# logicShifter2.net
KiCad netlist of a schematic drawn in EAGLE
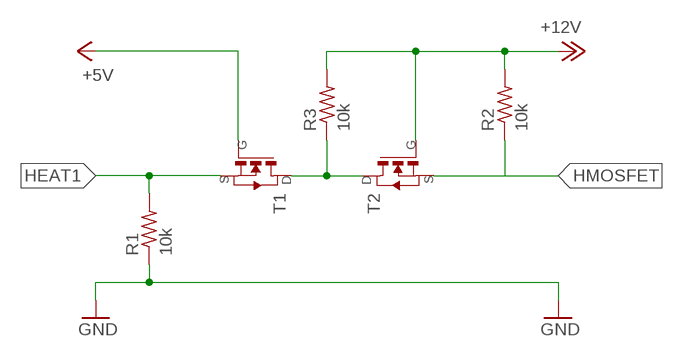
[diagram p0: schematic, sheet 1]

(export (version "E")
  (design (tool "Eeschema 10.0.6"))
  (components
    (comp (ref "R1")
      (value "10k")
      (footprint "eagle-import:R1206FAB")
      (libsource (lib "eagle-import") (part "RES-US1206FAB"))
    )
    (comp (ref "R2")
      (value "10k")
      (footprint "eagle-import:R1206FAB")
      (libsource (lib "eagle-import") (part "RES-US1206FAB"))
    )
    (comp (ref "R3")
      (value "10k")
      (footprint "eagle-import:R1206FAB")
      (libsource (lib "eagle-import") (part "RES-US1206FAB"))
    )
    (comp (ref "T1")
      (value "NMOSFETSOT23")
      (footprint "eagle-import:SOT-23")
      (libsource (lib "eagle-import") (part "NMOSFETSOT23"))
    )
    (comp (ref "T2")
      (value "NMOSFETSOT23")
      (footprint "eagle-import:SOT-23")
      (libsource (lib "eagle-import") (part "NMOSFETSOT23"))
    )
  )
  (nets
    (net (code "1") (name "+5V") (class "Default")
      (node (ref "T1") (pin "3") (pinfunction "G_3") (pintype "passive"))
    )
    (net (code "2") (name "+12V") (class "Default")
      (node (ref "R2") (pin "2") (pinfunction "2_2") (pintype "passive"))
      (node (ref "R3") (pin "2") (pinfunction "2_2") (pintype "passive"))
      (node (ref "T2") (pin "3") (pinfunction "G_3") (pintype "passive"))
    )
    (net (code "3") (name "GND") (class "Default")
      (node (ref "R1") (pin "1") (pinfunction "1_1") (pintype "passive"))
    )
    (net (code "4") (name "HEAT1") (class "Default")
      (node (ref "R1") (pin "2") (pinfunction "2_2") (pintype "passive"))
      (node (ref "T1") (pin "2") (pinfunction "S_2") (pintype "passive"))
    )
    (net (code "5") (name "HMOSFET") (class "Default")
      (node (ref "T2") (pin "2") (pinfunction "S_2") (pintype "passive"))
    )
    (net (code "6") (name "Net-(T1-D)") (class "Default")
      (node (ref "R3") (pin "1") (pinfunction "1_1") (pintype "passive"))
      (node (ref "T1") (pin "1") (pinfunction "D_1") (pintype "passive"))
      (node (ref "T2") (pin "1") (pinfunction "D_1") (pintype "passive"))
    )
    (net (code "7") (name "unconnected-(R2-Pad1)") (class "Default")
      (node (ref "R2") (pin "1") (pinfunction "1_1") (pintype "passive"))
    )
  )
)
